# INTP009_product.net
KiCad netlist of a schematic drawn in EAGLE
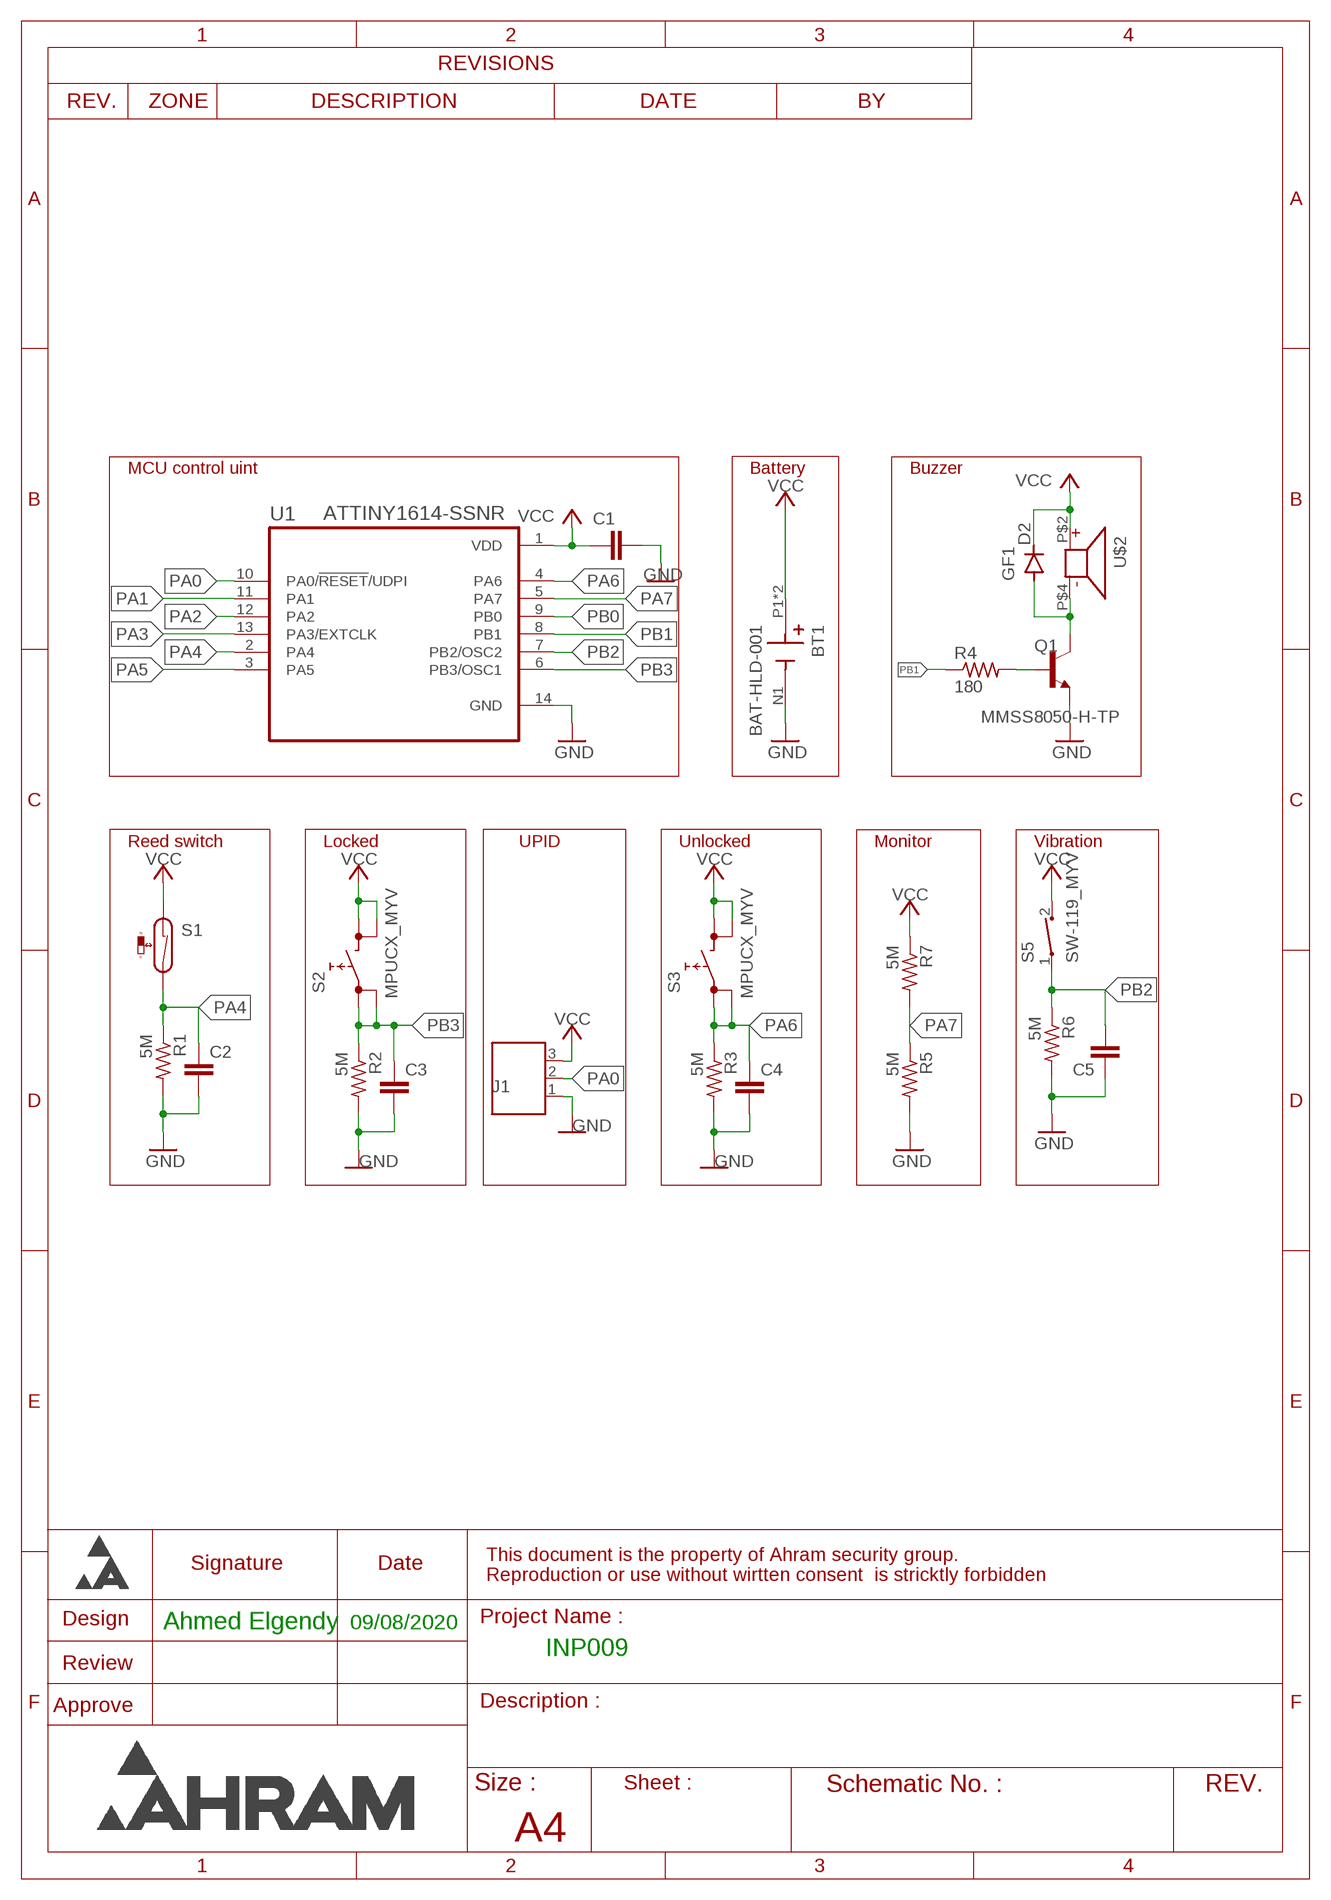
[diagram p0: schematic, sheet 1]

(export (version "E")
  (design (tool "Eeschema 10.0.6"))
  (components
    (comp (ref "BT1")
      (value "BAT-HLD-001")
      (footprint "eagle-import:BAT_BAT-HLD-001")
      (fields (field (name "MF") "Linx Technologies"))
      (libsource (lib "eagle-import") (part "BAT-HLD-001"))
    )
    (comp (ref "C1")
      (value "C-EUC0805K")
      (footprint "eagle-import:C0805K")
      (libsource (lib "eagle-import") (part "C-EUC0805K"))
    )
    (comp (ref "C2")
      (value "C-EUC0805K")
      (footprint "eagle-import:C0805K")
      (libsource (lib "eagle-import") (part "C-EUC0805K"))
    )
    (comp (ref "C3")
      (value "C-EUC0805K")
      (footprint "eagle-import:C0805K")
      (libsource (lib "eagle-import") (part "C-EUC0805K"))
    )
    (comp (ref "C4")
      (value "C-EUC0805K")
      (footprint "eagle-import:C0805K")
      (libsource (lib "eagle-import") (part "C-EUC0805K"))
    )
    (comp (ref "C5")
      (value "C-EUC0805K")
      (footprint "eagle-import:C0805K")
      (libsource (lib "eagle-import") (part "C-EUC0805K"))
    )
    (comp (ref "D2")
      (value "GF1")
      (footprint "eagle-import:SMA-DO214AC")
      (libsource (lib "eagle-import") (part "GF1"))
    )
    (comp (ref "J1")
      (value "691508110303")
      (footprint "eagle-import:691508110303")
      (libsource (lib "eagle-import") (part "691508110303"))
    )
    (comp (ref "Q1")
      (value "MMSS8050-H-TP")
      (footprint "eagle-import:TRANS_MMSS8050-H-TP")
      (fields (field (name "MF") "Micro Commercial"))
      (libsource (lib "eagle-import") (part "MMSS8050-H-TP"))
    )
    (comp (ref "R1")
      (value "5M")
      (footprint "eagle-import:M0805")
      (libsource (lib "eagle-import") (part "R-US_M0805"))
    )
    (comp (ref "R2")
      (value "5M")
      (footprint "eagle-import:M0805")
      (libsource (lib "eagle-import") (part "R-US_M0805"))
    )
    (comp (ref "R3")
      (value "5M")
      (footprint "eagle-import:M0805")
      (libsource (lib "eagle-import") (part "R-US_M0805"))
    )
    (comp (ref "R4")
      (value "180")
      (footprint "eagle-import:M0805")
      (libsource (lib "eagle-import") (part "R-US_M0805"))
    )
    (comp (ref "R5")
      (value "5M")
      (footprint "eagle-import:M0805")
      (libsource (lib "eagle-import") (part "R-US_M0805"))
    )
    (comp (ref "R6")
      (value "5M")
      (footprint "eagle-import:M0805")
      (libsource (lib "eagle-import") (part "R-US_M0805"))
    )
    (comp (ref "R7")
      (value "5M")
      (footprint "eagle-import:M0805")
      (libsource (lib "eagle-import") (part "R-US_M0805"))
    )
    (comp (ref "S1")
      (value "RI80SMDM-MYV")
      (footprint "eagle-import:RI80SMDM-0510-J1")
      (libsource (lib "eagle-import") (part "RI80SMDM-MYV"))
    )
    (comp (ref "S2")
      (value "MPUCX_MYV")
      (footprint "eagle-import:MPUCX_MYV")
      (libsource (lib "eagle-import") (part "MPUCX_MYV"))
    )
    (comp (ref "S3")
      (value "MPUCX_MYV")
      (footprint "eagle-import:MPUCX_MYV")
      (libsource (lib "eagle-import") (part "MPUCX_MYV"))
    )
    (comp (ref "S5")
      (value "SW-119_MYV")
      (footprint "eagle-import:SW-119")
      (libsource (lib "eagle-import") (part "SW-119_MYV"))
    )
    (comp (ref "U$2")
      (value "ST-A03BH_MYV")
      (footprint "eagle-import:ST-A03BH_MYV")
      (libsource (lib "eagle-import") (part "ST-A03BH_MYV"))
    )
    (comp (ref "U1")
      (value "ATTINY1614-SSNR")
      (footprint "eagle-import:SOIC127P600X175-14N")
      (fields (field (name "MF") "Microchip Technology"))
      (libsource (lib "eagle-import") (part "ATTINY1614-SSNR"))
    )
  )
  (nets
    (net (code "1") (name "GND") (class "Default")
      (node (ref "BT1") (pin "N1") (pinfunction "-_N1") (pintype "passive"))
      (node (ref "C1") (pin "2") (pinfunction "2_2") (pintype "passive"))
      (node (ref "C2") (pin "2") (pinfunction "2_2") (pintype "passive"))
      (node (ref "C3") (pin "2") (pinfunction "2_2") (pintype "passive"))
      (node (ref "C4") (pin "2") (pinfunction "2_2") (pintype "passive"))
      (node (ref "C5") (pin "1") (pinfunction "1_1") (pintype "passive"))
      (node (ref "J1") (pin "1") (pinfunction "1_1") (pintype "passive"))
      (node (ref "Q1") (pin "2") (pinfunction "E_2") (pintype "passive"))
      (node (ref "R1") (pin "2") (pinfunction "2_2") (pintype "passive"))
      (node (ref "R2") (pin "2") (pinfunction "2_2") (pintype "passive"))
      (node (ref "R3") (pin "2") (pinfunction "2_2") (pintype "passive"))
      (node (ref "R5") (pin "2") (pinfunction "2_2") (pintype "passive"))
      (node (ref "R6") (pin "2") (pinfunction "2_2") (pintype "passive"))
      (node (ref "U1") (pin "14") (pinfunction "GND_14") (pintype "power_in"))
    )
    (net (code "2") (name "Net-(Q1-B)") (class "Default")
      (node (ref "Q1") (pin "1") (pinfunction "B_1") (pintype "passive"))
      (node (ref "R4") (pin "2") (pinfunction "2_2") (pintype "passive"))
    )
    (net (code "3") (name "Net-(Q1-C)") (class "Default")
      (node (ref "D2") (pin "A") (pinfunction "A_A") (pintype "passive"))
      (node (ref "Q1") (pin "3") (pinfunction "C_3") (pintype "passive"))
      (node (ref "U$2") (pin "P$4") (pinfunction "2_P$4") (pintype "passive"))
    )
    (net (code "4") (name "PA0") (class "Default")
      (node (ref "J1") (pin "2") (pinfunction "2_2") (pintype "passive"))
      (node (ref "U1") (pin "10") (pinfunction "PA0/~{RESET}/UDPI_10") (pintype "bidirectional"))
    )
    (net (code "5") (name "PA1") (class "Default")
      (node (ref "U1") (pin "11") (pinfunction "PA1_11") (pintype "bidirectional"))
    )
    (net (code "6") (name "PA2") (class "Default")
      (node (ref "U1") (pin "12") (pinfunction "PA2_12") (pintype "bidirectional"))
    )
    (net (code "7") (name "PA3") (class "Default")
      (node (ref "U1") (pin "13") (pinfunction "PA3/EXTCLK_13") (pintype "bidirectional"))
    )
    (net (code "8") (name "PA4") (class "Default")
      (node (ref "C2") (pin "1") (pinfunction "1_1") (pintype "passive"))
      (node (ref "R1") (pin "1") (pinfunction "1_1") (pintype "passive"))
      (node (ref "S1") (pin "P$2") (pinfunction "2_P$2") (pintype "passive"))
      (node (ref "U1") (pin "2") (pinfunction "PA4_2") (pintype "bidirectional"))
    )
    (net (code "9") (name "PA5") (class "Default")
      (node (ref "U1") (pin "3") (pinfunction "PA5_3") (pintype "bidirectional"))
    )
    (net (code "10") (name "PA6") (class "Default")
      (node (ref "C4") (pin "1") (pinfunction "1_1") (pintype "passive"))
      (node (ref "R3") (pin "1") (pinfunction "1_1") (pintype "passive"))
      (node (ref "S3") (pin "1") (pinfunction "1_1") (pintype "passive"))
      (node (ref "S3") (pin "2") (pinfunction "2_2") (pintype "passive"))
      (node (ref "U1") (pin "4") (pinfunction "PA6_4") (pintype "bidirectional"))
    )
    (net (code "11") (name "PA7") (class "Default")
      (node (ref "R5") (pin "1") (pinfunction "1_1") (pintype "passive"))
      (node (ref "R7") (pin "2") (pinfunction "2_2") (pintype "passive"))
      (node (ref "U1") (pin "5") (pinfunction "PA7_5") (pintype "bidirectional"))
    )
    (net (code "12") (name "PB0") (class "Default")
      (node (ref "U1") (pin "9") (pinfunction "PB0_9") (pintype "bidirectional"))
    )
    (net (code "13") (name "PB1") (class "Default")
      (node (ref "R4") (pin "1") (pinfunction "1_1") (pintype "passive"))
      (node (ref "U1") (pin "8") (pinfunction "PB1_8") (pintype "bidirectional"))
    )
    (net (code "14") (name "PB2") (class "Default")
      (node (ref "C5") (pin "2") (pinfunction "2_2") (pintype "passive"))
      (node (ref "R6") (pin "1") (pinfunction "1_1") (pintype "passive"))
      (node (ref "S5") (pin "1") (pinfunction "1_1") (pintype "passive"))
      (node (ref "U1") (pin "7") (pinfunction "PB2/OSC2_7") (pintype "bidirectional"))
    )
    (net (code "15") (name "PB3") (class "Default")
      (node (ref "C3") (pin "1") (pinfunction "1_1") (pintype "passive"))
      (node (ref "R2") (pin "1") (pinfunction "1_1") (pintype "passive"))
      (node (ref "S2") (pin "1") (pinfunction "1_1") (pintype "passive"))
      (node (ref "S2") (pin "2") (pinfunction "2_2") (pintype "passive"))
      (node (ref "U1") (pin "6") (pinfunction "PB3/OSC1_6") (pintype "bidirectional"))
    )
    (net (code "16") (name "VCC") (class "Default")
      (node (ref "BT1") (pin "P1") (pinfunction "+_P1") (pintype "passive"))
      (node (ref "BT1") (pin "P2") (pinfunction "+_P2") (pintype "passive"))
      (node (ref "C1") (pin "1") (pinfunction "1_1") (pintype "passive"))
      (node (ref "D2") (pin "K") (pinfunction "C_K") (pintype "passive"))
      (node (ref "J1") (pin "3") (pinfunction "3_3") (pintype "passive"))
      (node (ref "R7") (pin "1") (pinfunction "1_1") (pintype "passive"))
      (node (ref "S1") (pin "P$1") (pinfunction "1_P$1") (pintype "passive"))
      (node (ref "S2") (pin "3") (pinfunction "3_3") (pintype "passive"))
      (node (ref "S2") (pin "4") (pinfunction "4_4") (pintype "passive"))
      (node (ref "S3") (pin "3") (pinfunction "3_3") (pintype "passive"))
      (node (ref "S3") (pin "4") (pinfunction "4_4") (pintype "passive"))
      (node (ref "S5") (pin "2") (pinfunction "2_2") (pintype "passive"))
      (node (ref "U$2") (pin "P$2") (pinfunction "1_P$2") (pintype "passive"))
      (node (ref "U1") (pin "1") (pinfunction "VDD_1") (pintype "power_in"))
    )
  )
)
